# TayDieuKhienWiFi_RF_n19_9_2019.net
KiCad netlist of a schematic drawn in EAGLE
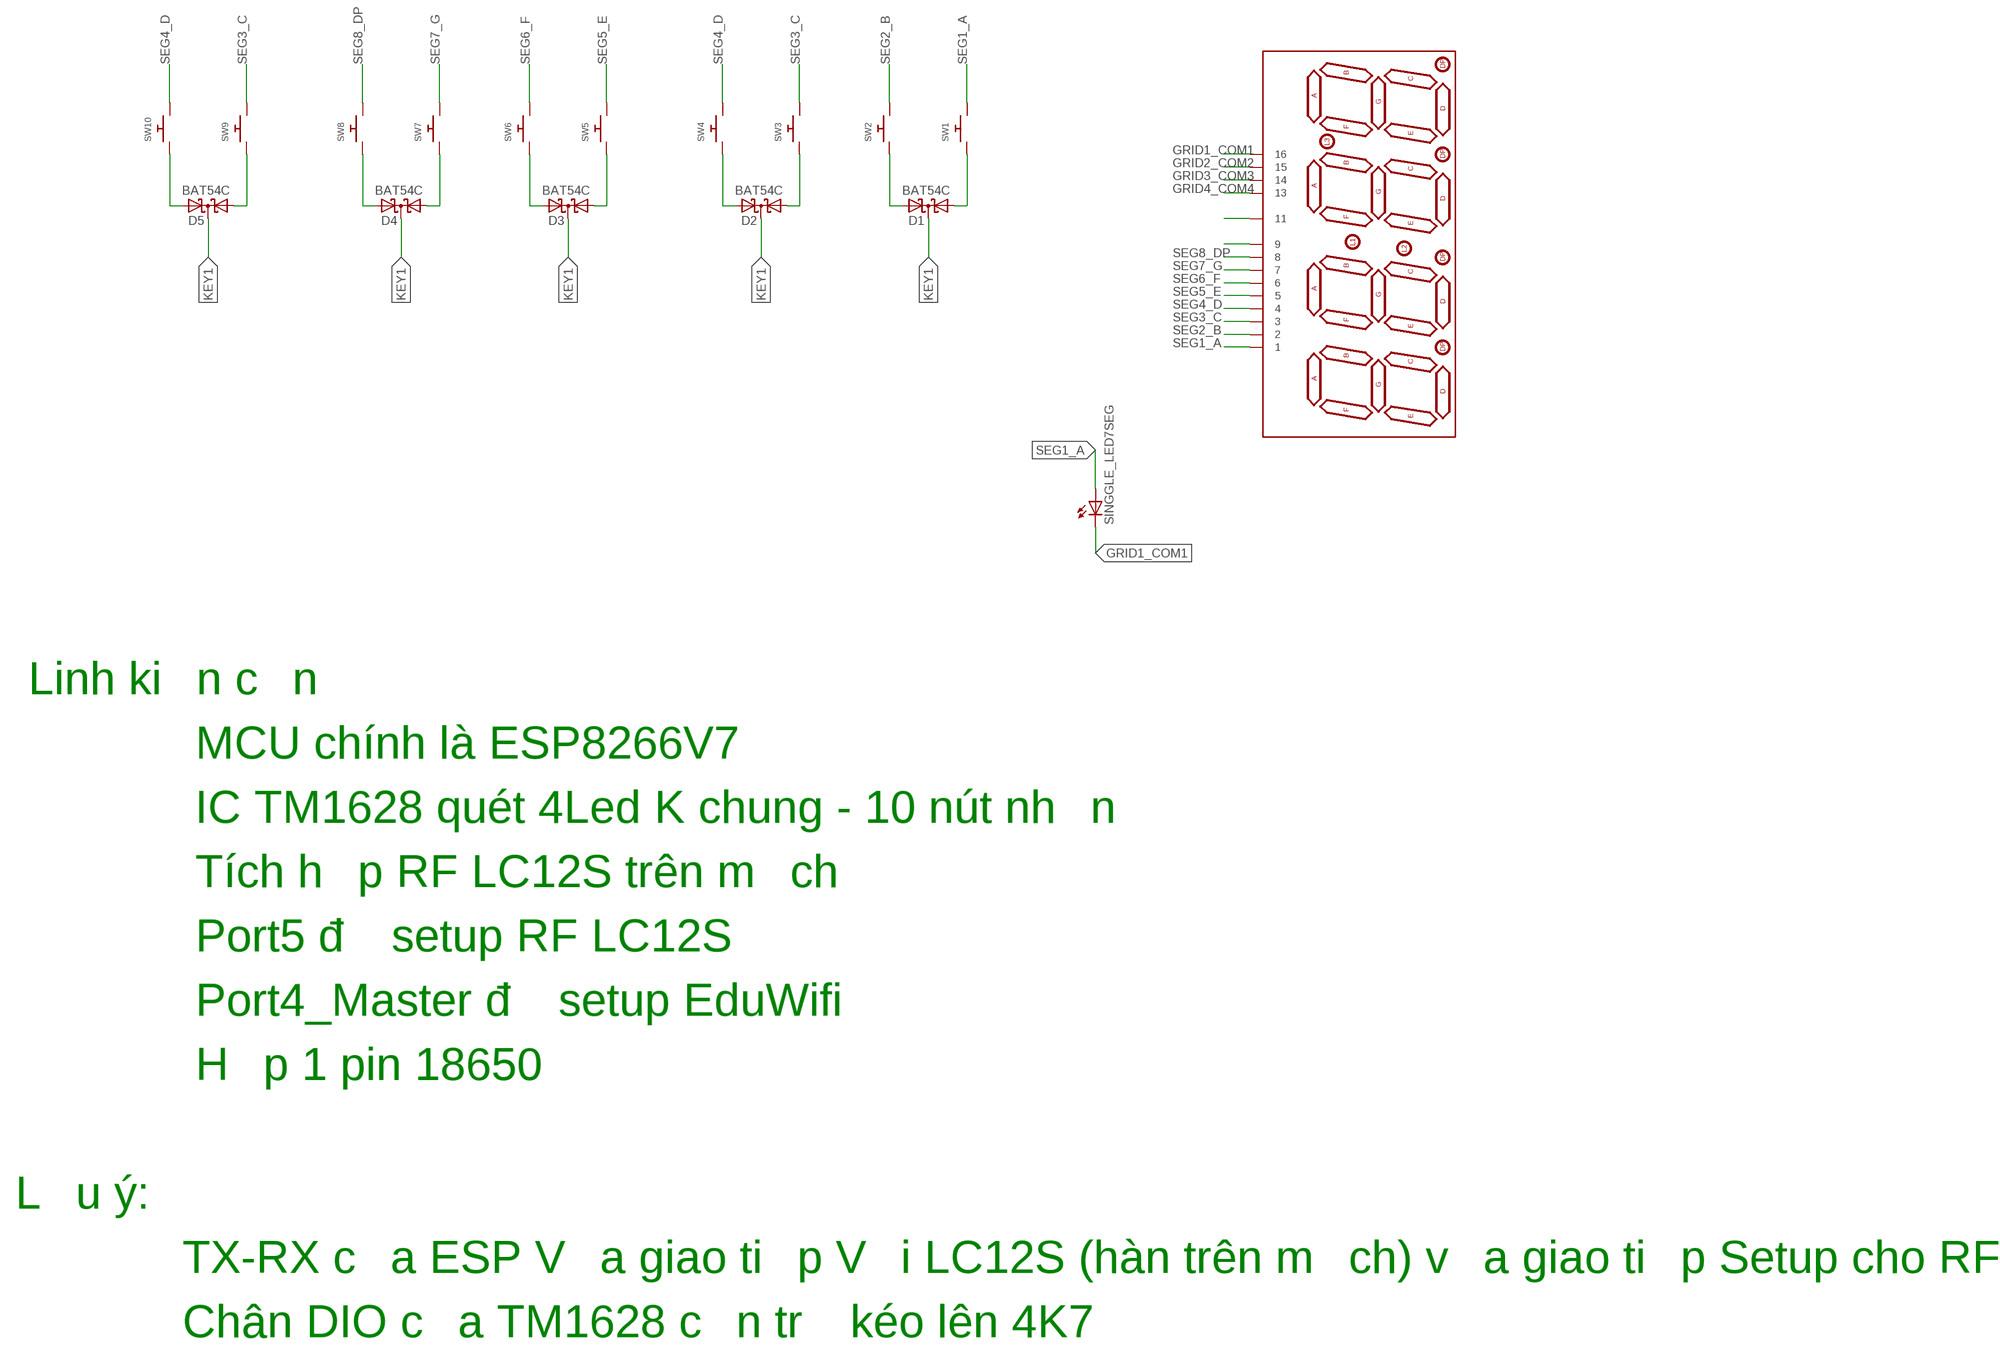
[diagram p0: schematic, sheet 1, part 1 of 2]
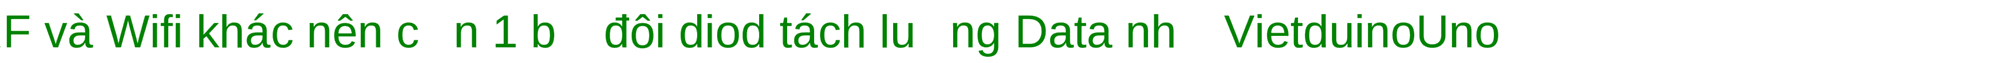
[diagram p1: schematic, sheet 1, part 2 of 2]

(export (version "E")
  (design (tool "Eeschema 10.0.6"))
  (components
    (comp (ref "D1")
      (value "BAT54C")
      (footprint "eagle-import:SOT23")
      (libsource (lib "eagle-import") (part "BAT54C"))
    )
    (comp (ref "D2")
      (value "BAT54C")
      (footprint "eagle-import:SOT23")
      (libsource (lib "eagle-import") (part "BAT54C"))
    )
    (comp (ref "D3")
      (value "BAT54C")
      (footprint "eagle-import:SOT23")
      (libsource (lib "eagle-import") (part "BAT54C"))
    )
    (comp (ref "D4")
      (value "BAT54C")
      (footprint "eagle-import:SOT23")
      (libsource (lib "eagle-import") (part "BAT54C"))
    )
    (comp (ref "D5")
      (value "BAT54C")
      (footprint "eagle-import:SOT23")
      (libsource (lib "eagle-import") (part "BAT54C"))
    )
    (comp (ref "SINGGLE_LED7SEG")
      (value "LEDCHIP-LED0603")
      (footprint "eagle-import:CHIP-LED0603")
      (libsource (lib "eagle-import") (part "LEDCHIP-LED0603"))
    )
    (comp (ref "SW1")
      (value "SWITCH_PUSHBUTTONC&K_KSS")
      (footprint "eagle-import:BTN_CK_KSS")
      (libsource (lib "eagle-import") (part "SWITCH_PUSHBUTTONC&K_KSS"))
    )
    (comp (ref "SW2")
      (value "SWITCH_PUSHBUTTONC&K_KSS")
      (footprint "eagle-import:BTN_CK_KSS")
      (libsource (lib "eagle-import") (part "SWITCH_PUSHBUTTONC&K_KSS"))
    )
    (comp (ref "SW3")
      (value "SWITCH_PUSHBUTTONC&K_KSS")
      (footprint "eagle-import:BTN_CK_KSS")
      (libsource (lib "eagle-import") (part "SWITCH_PUSHBUTTONC&K_KSS"))
    )
    (comp (ref "SW4")
      (value "SWITCH_PUSHBUTTONC&K_KSS")
      (footprint "eagle-import:BTN_CK_KSS")
      (libsource (lib "eagle-import") (part "SWITCH_PUSHBUTTONC&K_KSS"))
    )
    (comp (ref "SW5")
      (value "SWITCH_PUSHBUTTONC&K_KSS")
      (footprint "eagle-import:BTN_CK_KSS")
      (libsource (lib "eagle-import") (part "SWITCH_PUSHBUTTONC&K_KSS"))
    )
    (comp (ref "SW6")
      (value "SWITCH_PUSHBUTTONC&K_KSS")
      (footprint "eagle-import:BTN_CK_KSS")
      (libsource (lib "eagle-import") (part "SWITCH_PUSHBUTTONC&K_KSS"))
    )
    (comp (ref "SW7")
      (value "SWITCH_PUSHBUTTONC&K_KSS")
      (footprint "eagle-import:BTN_CK_KSS")
      (libsource (lib "eagle-import") (part "SWITCH_PUSHBUTTONC&K_KSS"))
    )
    (comp (ref "SW8")
      (value "SWITCH_PUSHBUTTONC&K_KSS")
      (footprint "eagle-import:BTN_CK_KSS")
      (libsource (lib "eagle-import") (part "SWITCH_PUSHBUTTONC&K_KSS"))
    )
    (comp (ref "SW9")
      (value "SWITCH_PUSHBUTTONC&K_KSS")
      (footprint "eagle-import:BTN_CK_KSS")
      (libsource (lib "eagle-import") (part "SWITCH_PUSHBUTTONC&K_KSS"))
    )
    (comp (ref "SW10")
      (value "SWITCH_PUSHBUTTONC&K_KSS")
      (footprint "eagle-import:BTN_CK_KSS")
      (libsource (lib "eagle-import") (part "SWITCH_PUSHBUTTONC&K_KSS"))
    )
    (comp (ref "U$1")
      (value "7-SEGMENT-4DIGIT")
      (footprint "eagle-import:7-SEGMENT-4DIGIT-YOUNGSUN")
      (libsource (lib "eagle-import") (part "7-SEGMENT-4DIGIT"))
    )
  )
  (nets
    (net (code "1") (name "/GRID2_COM2") (class "Default")
      (node (ref "U$1") (pin "15") (pinfunction "15_15") (pintype "bidirectional"))
    )
    (net (code "2") (name "/GRID3_COM3") (class "Default")
      (node (ref "U$1") (pin "14") (pinfunction "14_14") (pintype "bidirectional"))
    )
    (net (code "3") (name "/GRID4_COM4") (class "Default")
      (node (ref "U$1") (pin "13") (pinfunction "13_13") (pintype "bidirectional"))
    )
    (net (code "4") (name "/SEG2_B") (class "Default")
      (node (ref "SW2") (pin "P$2") (pinfunction "P$2_P$2") (pintype "passive"))
      (node (ref "U$1") (pin "2") (pinfunction "2_2") (pintype "bidirectional"))
    )
    (net (code "5") (name "/SEG3_C") (class "Default")
      (node (ref "SW3") (pin "P$2") (pinfunction "P$2_P$2") (pintype "passive"))
      (node (ref "SW9") (pin "P$2") (pinfunction "P$2_P$2") (pintype "passive"))
      (node (ref "U$1") (pin "3") (pinfunction "3_3") (pintype "bidirectional"))
    )
    (net (code "6") (name "/SEG4_D") (class "Default")
      (node (ref "SW10") (pin "P$2") (pinfunction "P$2_P$2") (pintype "passive"))
      (node (ref "SW4") (pin "P$2") (pinfunction "P$2_P$2") (pintype "passive"))
      (node (ref "U$1") (pin "4") (pinfunction "4_4") (pintype "bidirectional"))
    )
    (net (code "7") (name "/SEG5_E") (class "Default")
      (node (ref "SW5") (pin "P$2") (pinfunction "P$2_P$2") (pintype "passive"))
      (node (ref "U$1") (pin "5") (pinfunction "5_5") (pintype "bidirectional"))
    )
    (net (code "8") (name "/SEG6_F") (class "Default")
      (node (ref "SW6") (pin "P$2") (pinfunction "P$2_P$2") (pintype "passive"))
      (node (ref "U$1") (pin "6") (pinfunction "6_6") (pintype "bidirectional"))
    )
    (net (code "9") (name "/SEG7_G") (class "Default")
      (node (ref "SW7") (pin "P$2") (pinfunction "P$2_P$2") (pintype "passive"))
      (node (ref "U$1") (pin "7") (pinfunction "7_7") (pintype "bidirectional"))
    )
    (net (code "10") (name "/SEG8_DP") (class "Default")
      (node (ref "SW8") (pin "P$2") (pinfunction "P$2_P$2") (pintype "passive"))
      (node (ref "U$1") (pin "8") (pinfunction "8_8") (pintype "bidirectional"))
    )
    (net (code "11") (name "GRID1_COM1") (class "Default")
      (node (ref "SINGGLE_LED7SEG") (pin "C") (pinfunction "C_C") (pintype "passive"))
      (node (ref "U$1") (pin "16") (pinfunction "16_16") (pintype "bidirectional"))
    )
    (net (code "12") (name "KEY1") (class "Default")
      (node (ref "D1") (pin "3") (pinfunction "CC_3") (pintype "passive"))
      (node (ref "D2") (pin "3") (pinfunction "CC_3") (pintype "passive"))
      (node (ref "D3") (pin "3") (pinfunction "CC_3") (pintype "passive"))
      (node (ref "D4") (pin "3") (pinfunction "CC_3") (pintype "passive"))
      (node (ref "D5") (pin "3") (pinfunction "CC_3") (pintype "passive"))
    )
    (net (code "13") (name "Net-(D1-A1)") (class "Default")
      (node (ref "D1") (pin "1") (pinfunction "A1_1") (pintype "passive"))
      (node (ref "SW1") (pin "P$1") (pinfunction "P$1_P$1") (pintype "passive"))
    )
    (net (code "14") (name "Net-(D1-A2)") (class "Default")
      (node (ref "D1") (pin "2") (pinfunction "A2_2") (pintype "passive"))
      (node (ref "SW2") (pin "P$1") (pinfunction "P$1_P$1") (pintype "passive"))
    )
    (net (code "15") (name "Net-(D2-A1)") (class "Default")
      (node (ref "D2") (pin "1") (pinfunction "A1_1") (pintype "passive"))
      (node (ref "SW3") (pin "P$1") (pinfunction "P$1_P$1") (pintype "passive"))
    )
    (net (code "16") (name "Net-(D2-A2)") (class "Default")
      (node (ref "D2") (pin "2") (pinfunction "A2_2") (pintype "passive"))
      (node (ref "SW4") (pin "P$1") (pinfunction "P$1_P$1") (pintype "passive"))
    )
    (net (code "17") (name "Net-(D3-A1)") (class "Default")
      (node (ref "D3") (pin "1") (pinfunction "A1_1") (pintype "passive"))
      (node (ref "SW5") (pin "P$1") (pinfunction "P$1_P$1") (pintype "passive"))
    )
    (net (code "18") (name "Net-(D3-A2)") (class "Default")
      (node (ref "D3") (pin "2") (pinfunction "A2_2") (pintype "passive"))
      (node (ref "SW6") (pin "P$1") (pinfunction "P$1_P$1") (pintype "passive"))
    )
    (net (code "19") (name "Net-(D4-A1)") (class "Default")
      (node (ref "D4") (pin "1") (pinfunction "A1_1") (pintype "passive"))
      (node (ref "SW7") (pin "P$1") (pinfunction "P$1_P$1") (pintype "passive"))
    )
    (net (code "20") (name "Net-(D4-A2)") (class "Default")
      (node (ref "D4") (pin "2") (pinfunction "A2_2") (pintype "passive"))
      (node (ref "SW8") (pin "P$1") (pinfunction "P$1_P$1") (pintype "passive"))
    )
    (net (code "21") (name "Net-(D5-A1)") (class "Default")
      (node (ref "D5") (pin "1") (pinfunction "A1_1") (pintype "passive"))
      (node (ref "SW9") (pin "P$1") (pinfunction "P$1_P$1") (pintype "passive"))
    )
    (net (code "22") (name "Net-(D5-A2)") (class "Default")
      (node (ref "D5") (pin "2") (pinfunction "A2_2") (pintype "passive"))
      (node (ref "SW10") (pin "P$1") (pinfunction "P$1_P$1") (pintype "passive"))
    )
    (net (code "23") (name "SEG1_A") (class "Default")
      (node (ref "SINGGLE_LED7SEG") (pin "A") (pinfunction "A_A") (pintype "passive"))
      (node (ref "SW1") (pin "P$2") (pinfunction "P$2_P$2") (pintype "passive"))
      (node (ref "U$1") (pin "1") (pinfunction "1_1") (pintype "bidirectional"))
    )
    (net (code "24") (name "unconnected-(U$1-Pad9)") (class "Default")
      (node (ref "U$1") (pin "9") (pinfunction "9_9") (pintype "bidirectional"))
    )
    (net (code "25") (name "unconnected-(U$1-Pad11)") (class "Default")
      (node (ref "U$1") (pin "11") (pinfunction "11_11") (pintype "bidirectional"))
    )
  )
)
